# Motion.net
KiCad netlist of a schematic drawn in Altium Designer
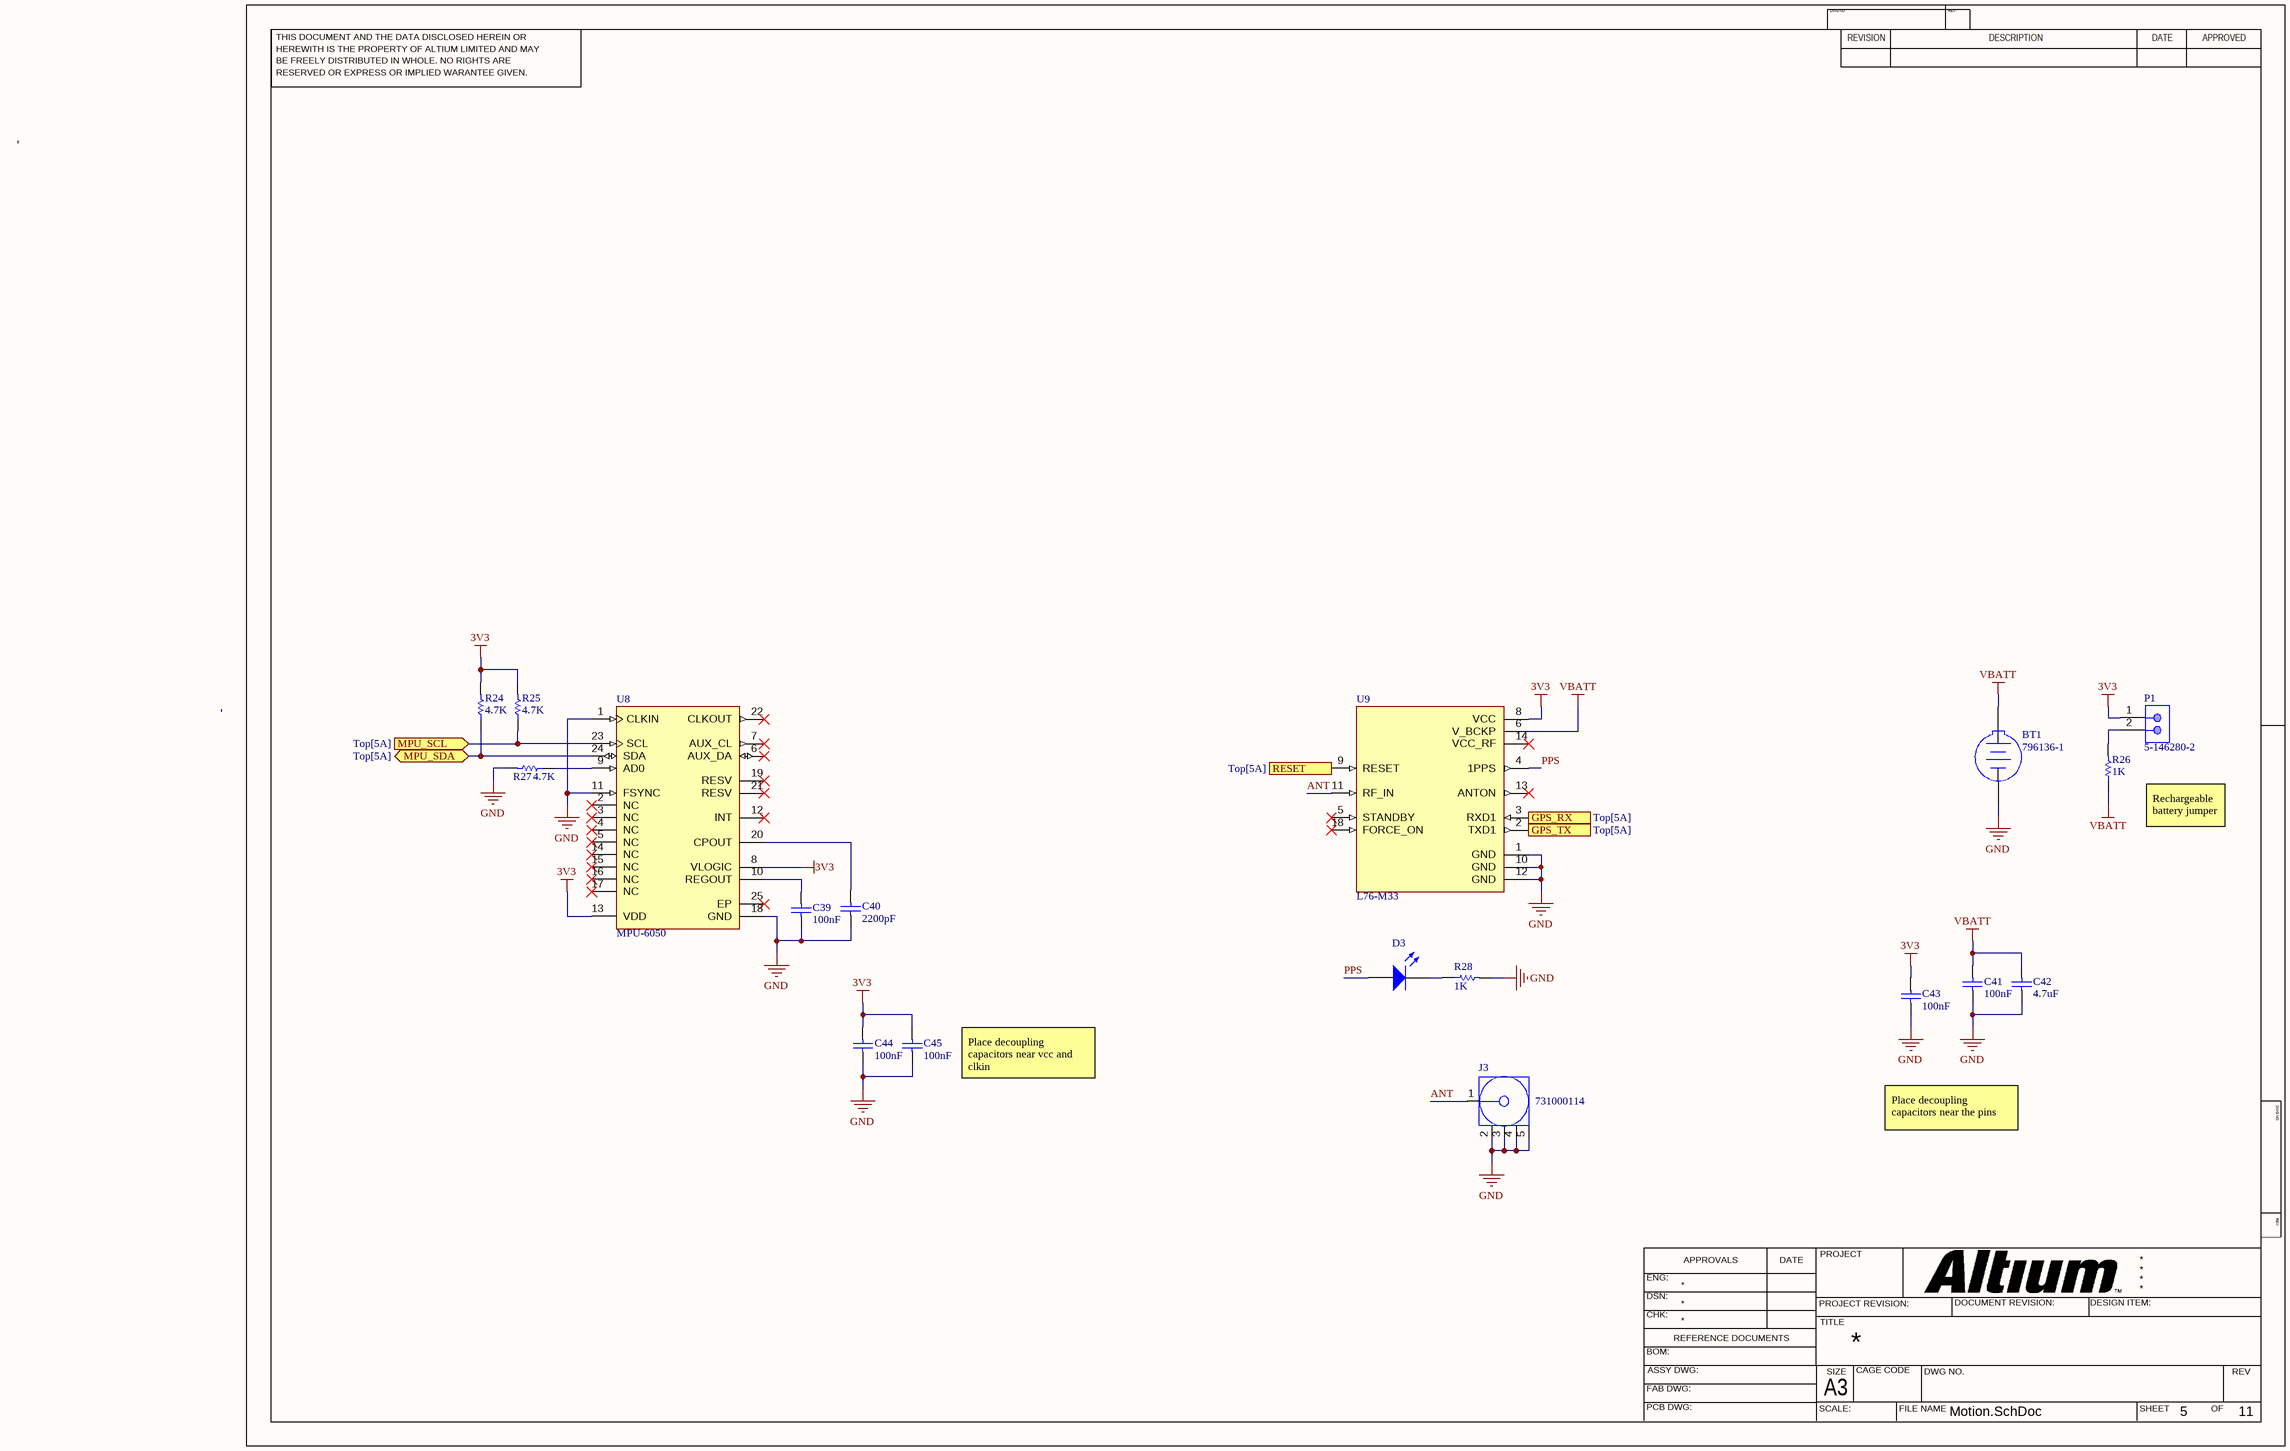
[diagram p0: Motion.SchDoc]

(export (version "E")
  (design (tool "Eeschema 10.0.6"))
  (components
    (comp (ref "BT1")
      (value "796136-1")
      (footprint "TECO-796136-1_V")
      (description "Battery Connector, 1 Cell, CR2032, 2-Pin SMD, RoHS, Tape and Reel")
      (libsource (lib "Altium Content Vault") (part "BATTERY-HOLDER-COIN-2"))
    )
    (comp (ref "C39")
      (value "100nF")
      (description "Capacitor")
      (libsource (lib "Simulation Generic Components") (part "Capacitor"))
    )
    (comp (ref "C40")
      (value "2200pF")
      (description "Capacitor")
      (libsource (lib "Simulation Generic Components") (part "Capacitor"))
    )
    (comp (ref "C41")
      (value "100nF")
      (description "Capacitor")
      (libsource (lib "Simulation Generic Components") (part "Capacitor"))
    )
    (comp (ref "C42")
      (value "4.7uF")
      (description "Capacitor")
      (libsource (lib "Simulation Generic Components") (part "Capacitor"))
    )
    (comp (ref "C43")
      (value "100nF")
      (description "Capacitor")
      (libsource (lib "Simulation Generic Components") (part "Capacitor"))
    )
    (comp (ref "C44")
      (value "100nF")
      (description "Capacitor")
      (libsource (lib "Simulation Generic Components") (part "Capacitor"))
    )
    (comp (ref "C45")
      (value "100nF")
      (description "Capacitor")
      (libsource (lib "Simulation Generic Components") (part "Capacitor"))
    )
    (comp (ref "D3")
      (value "Light-Emitting Diode")
      (libsource (lib "Simulation Generic Components") (part "LED"))
    )
    (comp (ref "J3")
      (value "731000114")
      (footprint "MOLX-731000114_V")
      (description "SMA Right-Angle PCB Jack Receptacle, Brass Body, Gold Plated, 50 Ohm, 5-Pin THD, RoHS, Tray")
      (fields (field (name "MANUFACTURER") "Molex"))
      (libsource (lib "Altium Content Vault") (part "CN-S-4F-RF5"))
    )
    (comp (ref "P1")
      (value "5-146280-2")
      (footprint "TECO-5-146280-2_V")
      (fields (field (name "MANUFACTURER") "TE Connectivity"))
      (libsource (lib "Altium Content Vault") (part "CN-1P-M-R2"))
    )
    (comp (ref "R24")
      (value "4.7K")
      (description "Resistor")
      (libsource (lib "Simulation Generic Components") (part "Resistor"))
    )
    (comp (ref "R25")
      (value "4.7K")
      (description "Resistor")
      (libsource (lib "Simulation Generic Components") (part "Resistor"))
    )
    (comp (ref "R26")
      (value "1K")
      (description "Resistor")
      (libsource (lib "Simulation Generic Components") (part "Resistor"))
    )
    (comp (ref "R27")
      (value "4.7K")
      (description "Resistor")
      (libsource (lib "Simulation Generic Components") (part "Resistor"))
    )
    (comp (ref "R28")
      (value "1K")
      (description "Resistor")
      (libsource (lib "Simulation Generic Components") (part "Resistor"))
    )
    (comp (ref "U8")
      (value "MPU-6050")
      (footprint "IS-QFN-24_V")
      (fields (field (name "MANUFACTURER") "InvenSense"))
      (libsource (lib "Altium Content Vault") (part "IS-MPU-6050-QFN-24"))
    )
    (comp (ref "U9")
      (value "L76-M33")
      (footprint "XCVR_L76-M33")
      (fields (field (name "MF") "Quectel"))
      (libsource (lib "GSSM Golf Cart") (part "L76-M33"))
    )
  )
  (nets
    (net (code "1") (name "/ANT") (class "Default")
      (node (ref "J3") (pin "1") (pinfunction "1_1") (pintype "passive"))
      (node (ref "U9") (pin "11") (pinfunction "RF_IN_11") (pintype "input"))
    )
    (net (code "2") (name "/GPS_RX") (class "Default")
      (node (ref "U9") (pin "3") (pinfunction "RXD1_3") (pintype "input"))
    )
    (net (code "3") (name "/GPS_TX") (class "Default")
      (node (ref "U9") (pin "2") (pinfunction "TXD1_2") (pintype "output"))
    )
    (net (code "4") (name "/MPU_SCL") (class "Default")
      (node (ref "R25") (pin "1") (pinfunction "1_1") (pintype "passive"))
      (node (ref "U8") (pin "23") (pinfunction "SCL_23") (pintype "input"))
    )
    (net (code "5") (name "/MPU_SDA") (class "Default")
      (node (ref "R24") (pin "1") (pinfunction "1_1") (pintype "passive"))
      (node (ref "U8") (pin "24") (pinfunction "SDA_24") (pintype "bidirectional"))
    )
    (net (code "6") (name "/PPS") (class "Default")
      (node (ref "D3") (pin "1") (pinfunction "A_1") (pintype "passive"))
      (node (ref "U9") (pin "4") (pinfunction "1PPS_4") (pintype "output"))
    )
    (net (code "7") (name "/RESET") (class "Default")
      (node (ref "U9") (pin "9") (pinfunction "RESET_9") (pintype "input"))
    )
    (net (code "8") (name "3V3") (class "Default")
      (node (ref "C43") (pin "2") (pinfunction "2_2") (pintype "passive"))
      (node (ref "C44") (pin "2") (pinfunction "2_2") (pintype "passive"))
      (node (ref "C45") (pin "2") (pinfunction "2_2") (pintype "passive"))
      (node (ref "P1") (pin "1") (pinfunction "1_1") (pintype "passive"))
      (node (ref "R24") (pin "2") (pinfunction "2_2") (pintype "passive"))
      (node (ref "R25") (pin "2") (pinfunction "2_2") (pintype "passive"))
      (node (ref "U8") (pin "13") (pinfunction "VDD_13") (pintype "power_in"))
      (node (ref "U8") (pin "8") (pinfunction "VLOGIC_8") (pintype "power_in"))
      (node (ref "U9") (pin "8") (pinfunction "VCC_8") (pintype "power_in"))
    )
    (net (code "9") (name "GND") (class "Default")
      (node (ref "BT1") (pin "2") (pinfunction "-_2") (pintype "passive"))
      (node (ref "C39") (pin "1") (pinfunction "1_1") (pintype "passive"))
      (node (ref "C40") (pin "1") (pinfunction "1_1") (pintype "passive"))
      (node (ref "C41") (pin "1") (pinfunction "1_1") (pintype "passive"))
      (node (ref "C42") (pin "1") (pinfunction "1_1") (pintype "passive"))
      (node (ref "C43") (pin "1") (pinfunction "1_1") (pintype "passive"))
      (node (ref "C44") (pin "1") (pinfunction "1_1") (pintype "passive"))
      (node (ref "C45") (pin "1") (pinfunction "1_1") (pintype "passive"))
      (node (ref "J3") (pin "2") (pinfunction "2_2") (pintype "passive"))
      (node (ref "J3") (pin "3") (pinfunction "3_3") (pintype "passive"))
      (node (ref "J3") (pin "4") (pinfunction "4_4") (pintype "passive"))
      (node (ref "J3") (pin "5") (pinfunction "5_5") (pintype "passive"))
      (node (ref "R27") (pin "2") (pinfunction "2_2") (pintype "passive"))
      (node (ref "R28") (pin "2") (pinfunction "2_2") (pintype "passive"))
      (node (ref "U8") (pin "1") (pinfunction "CLKIN_1") (pintype "input"))
      (node (ref "U8") (pin "11") (pinfunction "FSYNC_11") (pintype "input"))
      (node (ref "U8") (pin "18") (pinfunction "GND_18") (pintype "power_in"))
      (node (ref "U9") (pin "1") (pinfunction "GND_1") (pintype "power_in"))
      (node (ref "U9") (pin "10") (pinfunction "GND_10") (pintype "power_in"))
      (node (ref "U9") (pin "12") (pinfunction "GND_12") (pintype "power_in"))
    )
    (net (code "10") (name "Net-(D3-K)") (class "Default")
      (node (ref "D3") (pin "2") (pinfunction "K_2") (pintype "passive"))
      (node (ref "R28") (pin "1") (pinfunction "1_1") (pintype "passive"))
    )
    (net (code "11") (name "Net-(P1-Pad2)") (class "Default")
      (node (ref "P1") (pin "2") (pinfunction "2_2") (pintype "passive"))
      (node (ref "R26") (pin "2") (pinfunction "2_2") (pintype "passive"))
    )
    (net (code "12") (name "Net-(U8-AD0)") (class "Default")
      (node (ref "R27") (pin "1") (pinfunction "1_1") (pintype "passive"))
      (node (ref "U8") (pin "9") (pinfunction "AD0_9") (pintype "input"))
    )
    (net (code "13") (name "Net-(U8-CPOUT)") (class "Default")
      (node (ref "C40") (pin "2") (pinfunction "2_2") (pintype "passive"))
      (node (ref "U8") (pin "20") (pinfunction "CPOUT_20") (pintype "passive"))
    )
    (net (code "14") (name "Net-(U8-REGOUT)") (class "Default")
      (node (ref "C39") (pin "2") (pinfunction "2_2") (pintype "passive"))
      (node (ref "U8") (pin "10") (pinfunction "REGOUT_10") (pintype "passive"))
    )
    (net (code "15") (name "VBATT") (class "Default")
      (node (ref "BT1") (pin "1") (pinfunction "+_1") (pintype "passive"))
      (node (ref "C41") (pin "2") (pinfunction "2_2") (pintype "passive"))
      (node (ref "C42") (pin "2") (pinfunction "2_2") (pintype "passive"))
      (node (ref "R26") (pin "1") (pinfunction "1_1") (pintype "passive"))
      (node (ref "U9") (pin "6") (pinfunction "V_BCKP_6") (pintype "power_in"))
    )
    (net (code "16") (name "unconnected-(U8-AUX_CL-Pad7)") (class "Default")
      (node (ref "U8") (pin "7") (pinfunction "AUX_CL_7") (pintype "output+no_connect"))
    )
    (net (code "17") (name "unconnected-(U8-AUX_DA-Pad6)") (class "Default")
      (node (ref "U8") (pin "6") (pinfunction "AUX_DA_6") (pintype "bidirectional+no_connect"))
    )
    (net (code "18") (name "unconnected-(U8-CLKOUT-Pad22)") (class "Default")
      (node (ref "U8") (pin "22") (pinfunction "CLKOUT_22") (pintype "output+no_connect"))
    )
    (net (code "19") (name "unconnected-(U8-EP-Pad25)") (class "Default")
      (node (ref "U8") (pin "25") (pinfunction "EP_25") (pintype "power_in+no_connect"))
    )
    (net (code "20") (name "unconnected-(U8-INT-Pad12)") (class "Default")
      (node (ref "U8") (pin "12") (pinfunction "INT_12") (pintype "open_collector+no_connect"))
    )
    (net (code "21") (name "unconnected-(U8-NC-Pad2)") (class "Default")
      (node (ref "U8") (pin "2") (pinfunction "NC_2") (pintype "passive+no_connect"))
    )
    (net (code "22") (name "unconnected-(U8-NC-Pad3)") (class "Default")
      (node (ref "U8") (pin "3") (pinfunction "NC_3") (pintype "passive+no_connect"))
    )
    (net (code "23") (name "unconnected-(U8-NC-Pad4)") (class "Default")
      (node (ref "U8") (pin "4") (pinfunction "NC_4") (pintype "passive+no_connect"))
    )
    (net (code "24") (name "unconnected-(U8-NC-Pad5)") (class "Default")
      (node (ref "U8") (pin "5") (pinfunction "NC_5") (pintype "passive+no_connect"))
    )
    (net (code "25") (name "unconnected-(U8-NC-Pad14)") (class "Default")
      (node (ref "U8") (pin "14") (pinfunction "NC_14") (pintype "passive+no_connect"))
    )
    (net (code "26") (name "unconnected-(U8-NC-Pad15)") (class "Default")
      (node (ref "U8") (pin "15") (pinfunction "NC_15") (pintype "passive+no_connect"))
    )
    (net (code "27") (name "unconnected-(U8-NC-Pad16)") (class "Default")
      (node (ref "U8") (pin "16") (pinfunction "NC_16") (pintype "passive+no_connect"))
    )
    (net (code "28") (name "unconnected-(U8-NC-Pad17)") (class "Default")
      (node (ref "U8") (pin "17") (pinfunction "NC_17") (pintype "passive+no_connect"))
    )
    (net (code "29") (name "unconnected-(U8-RESV-Pad19)") (class "Default")
      (node (ref "U8") (pin "19") (pinfunction "RESV_19") (pintype "passive+no_connect"))
    )
    (net (code "30") (name "unconnected-(U8-RESV-Pad21)") (class "Default")
      (node (ref "U8") (pin "21") (pinfunction "RESV_21") (pintype "passive+no_connect"))
    )
    (net (code "31") (name "unconnected-(U9-ANTON-Pad13)") (class "Default")
      (node (ref "U9") (pin "13") (pinfunction "ANTON_13") (pintype "output+no_connect"))
    )
    (net (code "32") (name "unconnected-(U9-FORCE_ON-Pad18)") (class "Default")
      (node (ref "U9") (pin "18") (pinfunction "FORCE_ON_18") (pintype "input+no_connect"))
    )
    (net (code "33") (name "unconnected-(U9-STANDBY-Pad5)") (class "Default")
      (node (ref "U9") (pin "5") (pinfunction "STANDBY_5") (pintype "input+no_connect"))
    )
    (net (code "34") (name "unconnected-(U9-VCC_RF-Pad14)") (class "Default")
      (node (ref "U9") (pin "14") (pinfunction "VCC_RF_14") (pintype "power_in+no_connect"))
    )
  )
)
